# PM12_P1V8.net
KiCad netlist of a schematic drawn in Altium Designer
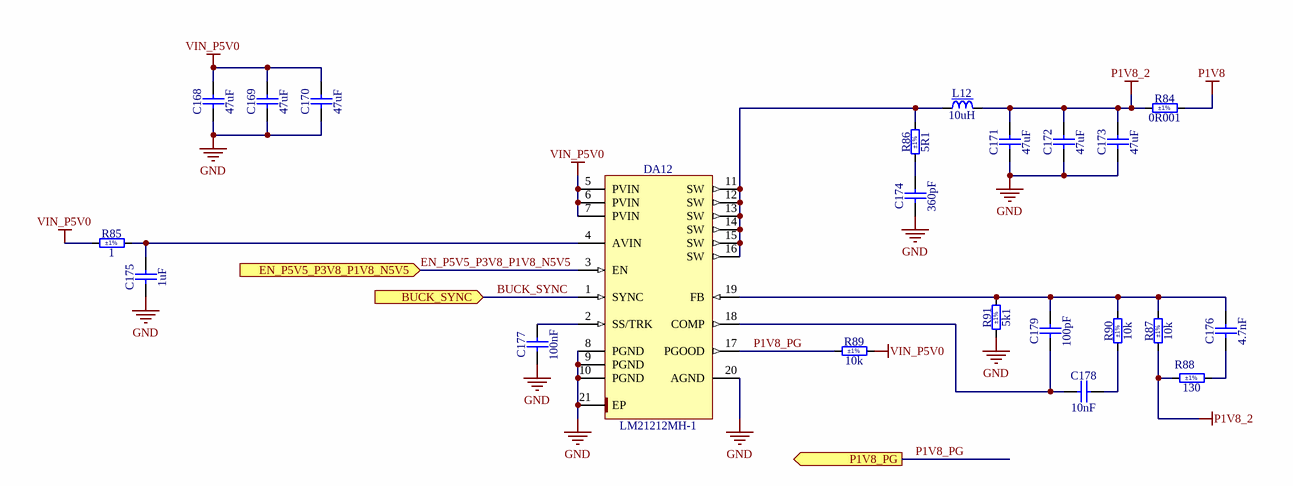
[diagram p0: PM12_P1V8.SchDoc]

(export (version "E")
  (design (tool "Eeschema 10.0.6"))
  (components
    (comp (ref "C168")
      (value "47uF")
      (footprint "CAPC3225X270N")
      (description "Non-polarised capacitor")
      (fields
        (field (name "PART NUMBER") "CC1210_47UF_16V_20%_X5R")
        (field (name "VOLTAGE") "16V")
        (field (name "AUTHOR") "CERN DEM MR")
      )
      (libsource (lib "Capacitors") (part "Capacitor - non polarized"))
    )
    (comp (ref "C169")
      (value "47uF")
      (footprint "CAPC3225X270N")
      (description "Non-polarised capacitor")
      (fields
        (field (name "PART NUMBER") "CC1210_47UF_16V_20%_X5R")
        (field (name "VOLTAGE") "16V")
        (field (name "AUTHOR") "CERN DEM MR")
      )
      (libsource (lib "Capacitors") (part "Capacitor - non polarized"))
    )
    (comp (ref "C170")
      (value "47uF")
      (footprint "CAPC3225X270N")
      (description "Non-polarised capacitor")
      (fields
        (field (name "PART NUMBER") "CC1210_47UF_16V_20%_X5R")
        (field (name "VOLTAGE") "16V")
        (field (name "AUTHOR") "CERN DEM MR")
      )
      (libsource (lib "Capacitors") (part "Capacitor - non polarized"))
    )
    (comp (ref "C171")
      (value "47uF")
      (footprint "CAPC3225X270N")
      (description "Non-polarised capacitor")
      (fields
        (field (name "PART NUMBER") "CC1210_47UF_16V_20%_X5R")
        (field (name "VOLTAGE") "16V")
        (field (name "AUTHOR") "CERN DEM MR")
      )
      (libsource (lib "Capacitors") (part "Capacitor - non polarized"))
    )
    (comp (ref "C172")
      (value "47uF")
      (footprint "CAPC3225X270N")
      (description "Non-polarised capacitor")
      (fields
        (field (name "PART NUMBER") "CC1210_47UF_16V_20%_X5R")
        (field (name "VOLTAGE") "16V")
        (field (name "AUTHOR") "CERN DEM MR")
      )
      (libsource (lib "Capacitors") (part "Capacitor - non polarized"))
    )
    (comp (ref "C173")
      (value "47uF")
      (footprint "CAPC3225X270N")
      (description "Non-polarised capacitor")
      (fields
        (field (name "PART NUMBER") "CC1210_47UF_16V_20%_X5R")
        (field (name "VOLTAGE") "16V")
        (field (name "AUTHOR") "CERN DEM MR")
      )
      (libsource (lib "Capacitors") (part "Capacitor - non polarized"))
    )
    (comp (ref "C174")
      (value "360pF")
      (footprint "CAPC2013X145N")
      (description "Non-polarised capacitor")
      (fields
        (field (name "PART NUMBER") "CC0805_360PF_50V_5%_C0G")
        (field (name "VOLTAGE") "50V")
        (field (name "AUTHOR") "CERN DEM HF")
      )
      (libsource (lib "Capacitors") (part "Capacitor - non polarized"))
    )
    (comp (ref "C175")
      (value "1uF")
      (footprint "CAPC2012X140N")
      (description "Non-polarised capacitor")
      (fields
        (field (name "PART NUMBER") "CC0805_1UF_25V_10%_X7R")
        (field (name "VOLTAGE") "25V")
        (field (name "AUTHOR") "CERN DEM JLC")
      )
      (libsource (lib "Capacitors") (part "Capacitor - non polarized"))
    )
    (comp (ref "C176")
      (value "4.7nF")
      (footprint "CAPC2012X135N")
      (description "Non-polarised capacitor")
      (fields
        (field (name "PART NUMBER") "CC0805_4.7NF_50V_10%_X7R")
        (field (name "VOLTAGE") "50V")
        (field (name "AUTHOR") "CERN DEM JLC")
      )
      (libsource (lib "Capacitors") (part "Capacitor - non polarized"))
    )
    (comp (ref "C177")
      (value "100nF")
      (footprint "CAPC2012X135N")
      (description "Non-polarised capacitor")
      (fields
        (field (name "PART NUMBER") "CC0805_100NF_50V_10%_X7R")
        (field (name "VOLTAGE") "50V")
        (field (name "AUTHOR") "CERN DEM JLC")
      )
      (libsource (lib "Capacitors") (part "Capacitor - non polarized"))
    )
    (comp (ref "C178")
      (value "10nF")
      (footprint "CAPC2012X135N")
      (description "Non-polarised capacitor")
      (fields
        (field (name "PART NUMBER") "CC0805_10NF_50V_10%_X7R")
        (field (name "VOLTAGE") "50V")
        (field (name "AUTHOR") "CERN DEM JLC")
      )
      (libsource (lib "Capacitors") (part "Capacitor - non polarized"))
    )
    (comp (ref "C179")
      (value "100pF")
      (footprint "CAPC2012X135N")
      (description "Non-polarised capacitor")
      (fields
        (field (name "PART NUMBER") "CC0805_100PF_50V_5%_NP0")
        (field (name "VOLTAGE") "50V")
        (field (name "AUTHOR") "CERN DEM JLC")
      )
      (libsource (lib "Capacitors") (part "Capacitor - non polarized"))
    )
    (comp (ref "DA12")
      (value "LM21212MH-1")
      (footprint "TEXAS_PWP0020AA")
      (description "2.95-V To 5.5-V, 12-A, Voltage-Mode Synchronous Buck Regulator with Frequency Synchronization")
      (fields (field (name "MANUFACTURER") "TEXAS INSTRUMENTS") (field (name "AUTHOR") "CERN DEM HF"))
      (libsource (lib "ICs And Semiconductors") (part "LM21212"))
    )
    (comp (ref "L12")
      (value "10uH")
      (footprint "IND_VISHAY_IHPL4040DZ-01")
      (description "Inductor With Core")
      (fields
        (field (name "PART NUMBER") "IND4040_10UH_20%_VISHAY_IHLP-4040DZ-01")
        (field (name "POWER") "6.8A")
        (field (name "AUTHOR") "CERN DEM HF")
      )
      (libsource (lib "Inductors & Transformers") (part "Inductor With Magnetic core"))
    )
    (comp (ref "R84")
      (value "0R001")
      (footprint "RESC_BOURNS_CRE2512_0R001-0R004")
      (description "Resistor - 1%")
      (fields
        (field (name "TOLERANCE") "±1%")
        (field (name "PART NUMBER") "R2512_0R001_1%_3W_50PPM_BOURNS_CRE2512")
        (field (name "POWER") "3W")
        (field (name "AUTHOR") "CERN DEM BC")
      )
      (libsource (lib "Resistors") (part "Resistor - 1%"))
    )
    (comp (ref "R85")
      (value "1")
      (footprint "RESC2012X60N")
      (description "Resistor - 1%")
      (fields
        (field (name "TOLERANCE") "±1%")
        (field (name "PART NUMBER") "R0805_1R_1%_0.125W_100PPM")
        (field (name "POWER") "0.125W")
        (field (name "AUTHOR") "CERN DEM HF")
      )
      (libsource (lib "Resistors") (part "Resistor - 1%"))
    )
    (comp (ref "R86")
      (value "5R1")
      (footprint "RESC2012X60N")
      (description "Resistor - 1%")
      (fields
        (field (name "TOLERANCE") "±1%")
        (field (name "PART NUMBER") "R0805_5R1_1%_0.125W_100PPM")
        (field (name "POWER") "0.125W")
        (field (name "AUTHOR") "CERN DEM HF")
      )
      (libsource (lib "Resistors") (part "Resistor - 1%"))
    )
    (comp (ref "R87")
      (value "10k")
      (footprint "RESC2012X60N")
      (description "Resistor - 1%")
      (fields
        (field (name "TOLERANCE") "±1%")
        (field (name "PART NUMBER") "R0805_10K_1%_0.125W_100PPM")
        (field (name "POWER") "0.125W")
        (field (name "AUTHOR") "CERN DEM JLC")
      )
      (libsource (lib "Resistors") (part "Resistor - 1%"))
    )
    (comp (ref "R88")
      (value "130")
      (footprint "RESC2012X60N")
      (description "Resistor - 1%")
      (fields
        (field (name "TOLERANCE") "±1%")
        (field (name "PART NUMBER") "R0805_130R_1%_0.125W_100PPM")
        (field (name "POWER") "0.125W")
        (field (name "AUTHOR") "CERN DEM JLC")
      )
      (libsource (lib "Resistors") (part "Resistor - 1%"))
    )
    (comp (ref "R89")
      (value "10k")
      (footprint "RESC2012X60N")
      (description "Resistor - 1%")
      (fields
        (field (name "TOLERANCE") "±1%")
        (field (name "PART NUMBER") "R0805_10K_1%_0.125W_100PPM")
        (field (name "POWER") "0.125W")
        (field (name "AUTHOR") "CERN DEM JLC")
      )
      (libsource (lib "Resistors") (part "Resistor - 1%"))
    )
    (comp (ref "R90")
      (value "10k")
      (footprint "RESC2012X60N")
      (description "Resistor - 1%")
      (fields
        (field (name "TOLERANCE") "±1%")
        (field (name "PART NUMBER") "R0805_10K_1%_0.125W_100PPM")
        (field (name "POWER") "0.125W")
        (field (name "AUTHOR") "CERN DEM JLC")
      )
      (libsource (lib "Resistors") (part "Resistor - 1%"))
    )
    (comp (ref "R91")
      (value "5k1")
      (footprint "RESC2012X60N")
      (description "Resistor - 1%")
      (fields
        (field (name "TOLERANCE") "±1%")
        (field (name "PART NUMBER") "R0805_5K1_1%_0.125W_100PPM")
        (field (name "POWER") "0.125W")
        (field (name "AUTHOR") "CERN DEM JLC")
      )
      (libsource (lib "Resistors") (part "Resistor - 1%"))
    )
  )
  (nets
    (net (code "1") (name "/BUCK_SYNC") (class "Default")
      (node (ref "DA12") (pin "1") (pinfunction "SYNC_1") (pintype "input"))
    )
    (net (code "2") (name "/EN_P5V5_P3V8_P1V8_N5V5") (class "Default")
      (node (ref "DA12") (pin "3") (pinfunction "EN_3") (pintype "input"))
    )
    (net (code "3") (name "/P1V8_PG") (class "Default")
      (node (ref "DA12") (pin "17") (pinfunction "PGOOD_17") (pintype "output"))
      (node (ref "R89") (pin "1") (pinfunction "1_1") (pintype "passive"))
    )
    (net (code "4") (name "GND") (class "Default")
      (node (ref "C168") (pin "1") (pinfunction "1_1") (pintype "passive"))
      (node (ref "C169") (pin "1") (pinfunction "1_1") (pintype "passive"))
      (node (ref "C170") (pin "1") (pinfunction "1_1") (pintype "passive"))
      (node (ref "C171") (pin "1") (pinfunction "1_1") (pintype "passive"))
      (node (ref "C172") (pin "1") (pinfunction "1_1") (pintype "passive"))
      (node (ref "C173") (pin "1") (pinfunction "1_1") (pintype "passive"))
      (node (ref "C174") (pin "1") (pinfunction "1_1") (pintype "passive"))
      (node (ref "C175") (pin "1") (pinfunction "1_1") (pintype "passive"))
      (node (ref "C177") (pin "1") (pinfunction "1_1") (pintype "passive"))
      (node (ref "DA12") (pin "10") (pinfunction "PGND_10") (pintype "power_in"))
      (node (ref "DA12") (pin "20") (pinfunction "AGND_20") (pintype "power_in"))
      (node (ref "DA12") (pin "21") (pinfunction "EP_21") (pintype "power_in"))
      (node (ref "DA12") (pin "8") (pinfunction "PGND_8") (pintype "power_in"))
      (node (ref "DA12") (pin "9") (pinfunction "PGND_9") (pintype "power_in"))
      (node (ref "R91") (pin "1") (pinfunction "1_1") (pintype "passive"))
    )
    (net (code "5") (name "Net-(C174-Pad2)") (class "Default")
      (node (ref "C174") (pin "2") (pinfunction "2_2") (pintype "passive"))
      (node (ref "R86") (pin "1") (pinfunction "1_1") (pintype "passive"))
    )
    (net (code "6") (name "Net-(C176-Pad1)") (class "Default")
      (node (ref "C176") (pin "1") (pinfunction "1_1") (pintype "passive"))
      (node (ref "R88") (pin "1") (pinfunction "1_1") (pintype "passive"))
    )
    (net (code "7") (name "Net-(C178-Pad1)") (class "Default")
      (node (ref "C178") (pin "1") (pinfunction "1_1") (pintype "passive"))
      (node (ref "R90") (pin "1") (pinfunction "1_1") (pintype "passive"))
    )
    (net (code "8") (name "Net-(DA12-AVIN)") (class "Default")
      (node (ref "C175") (pin "2") (pinfunction "2_2") (pintype "passive"))
      (node (ref "DA12") (pin "4") (pinfunction "AVIN_4") (pintype "power_in"))
      (node (ref "R85") (pin "2") (pinfunction "2_2") (pintype "passive"))
    )
    (net (code "9") (name "Net-(DA12-COMP)") (class "Default")
      (node (ref "C178") (pin "2") (pinfunction "2_2") (pintype "passive"))
      (node (ref "C179") (pin "1") (pinfunction "1_1") (pintype "passive"))
      (node (ref "DA12") (pin "18") (pinfunction "COMP_18") (pintype "output"))
    )
    (net (code "10") (name "Net-(DA12-FB)") (class "Default")
      (node (ref "C176") (pin "2") (pinfunction "2_2") (pintype "passive"))
      (node (ref "C179") (pin "2") (pinfunction "2_2") (pintype "passive"))
      (node (ref "DA12") (pin "19") (pinfunction "FB_19") (pintype "input"))
      (node (ref "R87") (pin "2") (pinfunction "2_2") (pintype "passive"))
      (node (ref "R90") (pin "2") (pinfunction "2_2") (pintype "passive"))
      (node (ref "R91") (pin "2") (pinfunction "2_2") (pintype "passive"))
    )
    (net (code "11") (name "Net-(DA12-SS{slash}TRK)") (class "Default")
      (node (ref "C177") (pin "2") (pinfunction "2_2") (pintype "passive"))
      (node (ref "DA12") (pin "2") (pinfunction "SS/TRK_2") (pintype "input"))
    )
    (net (code "12") (name "Net-(DA12-SW-Pad11)") (class "Default")
      (node (ref "DA12") (pin "11") (pinfunction "SW_11") (pintype "output"))
      (node (ref "DA12") (pin "12") (pinfunction "SW_12") (pintype "output"))
      (node (ref "DA12") (pin "13") (pinfunction "SW_13") (pintype "output"))
      (node (ref "DA12") (pin "14") (pinfunction "SW_14") (pintype "output"))
      (node (ref "DA12") (pin "15") (pinfunction "SW_15") (pintype "output"))
      (node (ref "DA12") (pin "16") (pinfunction "SW_16") (pintype "output"))
      (node (ref "L12") (pin "1") (pinfunction "1_1") (pintype "passive"))
      (node (ref "R86") (pin "2") (pinfunction "2_2") (pintype "passive"))
    )
    (net (code "13") (name "P1V8") (class "Default")
      (node (ref "R84") (pin "2") (pinfunction "2_2") (pintype "passive"))
    )
    (net (code "14") (name "P1V8_2") (class "Default")
      (node (ref "C171") (pin "2") (pinfunction "2_2") (pintype "passive"))
      (node (ref "C172") (pin "2") (pinfunction "2_2") (pintype "passive"))
      (node (ref "C173") (pin "2") (pinfunction "2_2") (pintype "passive"))
      (node (ref "L12") (pin "2") (pinfunction "2_2") (pintype "passive"))
      (node (ref "R84") (pin "1") (pinfunction "1_1") (pintype "passive"))
      (node (ref "R87") (pin "1") (pinfunction "1_1") (pintype "passive"))
      (node (ref "R88") (pin "2") (pinfunction "2_2") (pintype "passive"))
    )
    (net (code "15") (name "VIN_P5V0") (class "Default")
      (node (ref "C168") (pin "2") (pinfunction "2_2") (pintype "passive"))
      (node (ref "C169") (pin "2") (pinfunction "2_2") (pintype "passive"))
      (node (ref "C170") (pin "2") (pinfunction "2_2") (pintype "passive"))
      (node (ref "DA12") (pin "5") (pinfunction "PVIN_5") (pintype "power_in"))
      (node (ref "DA12") (pin "6") (pinfunction "PVIN_6") (pintype "power_in"))
      (node (ref "DA12") (pin "7") (pinfunction "PVIN_7") (pintype "power_in"))
      (node (ref "R85") (pin "1") (pinfunction "1_1") (pintype "passive"))
      (node (ref "R89") (pin "2") (pinfunction "2_2") (pintype "passive"))
    )
  )
)
